# PowerSup24V18-20A.net
KiCad netlist of a schematic drawn in EAGLE
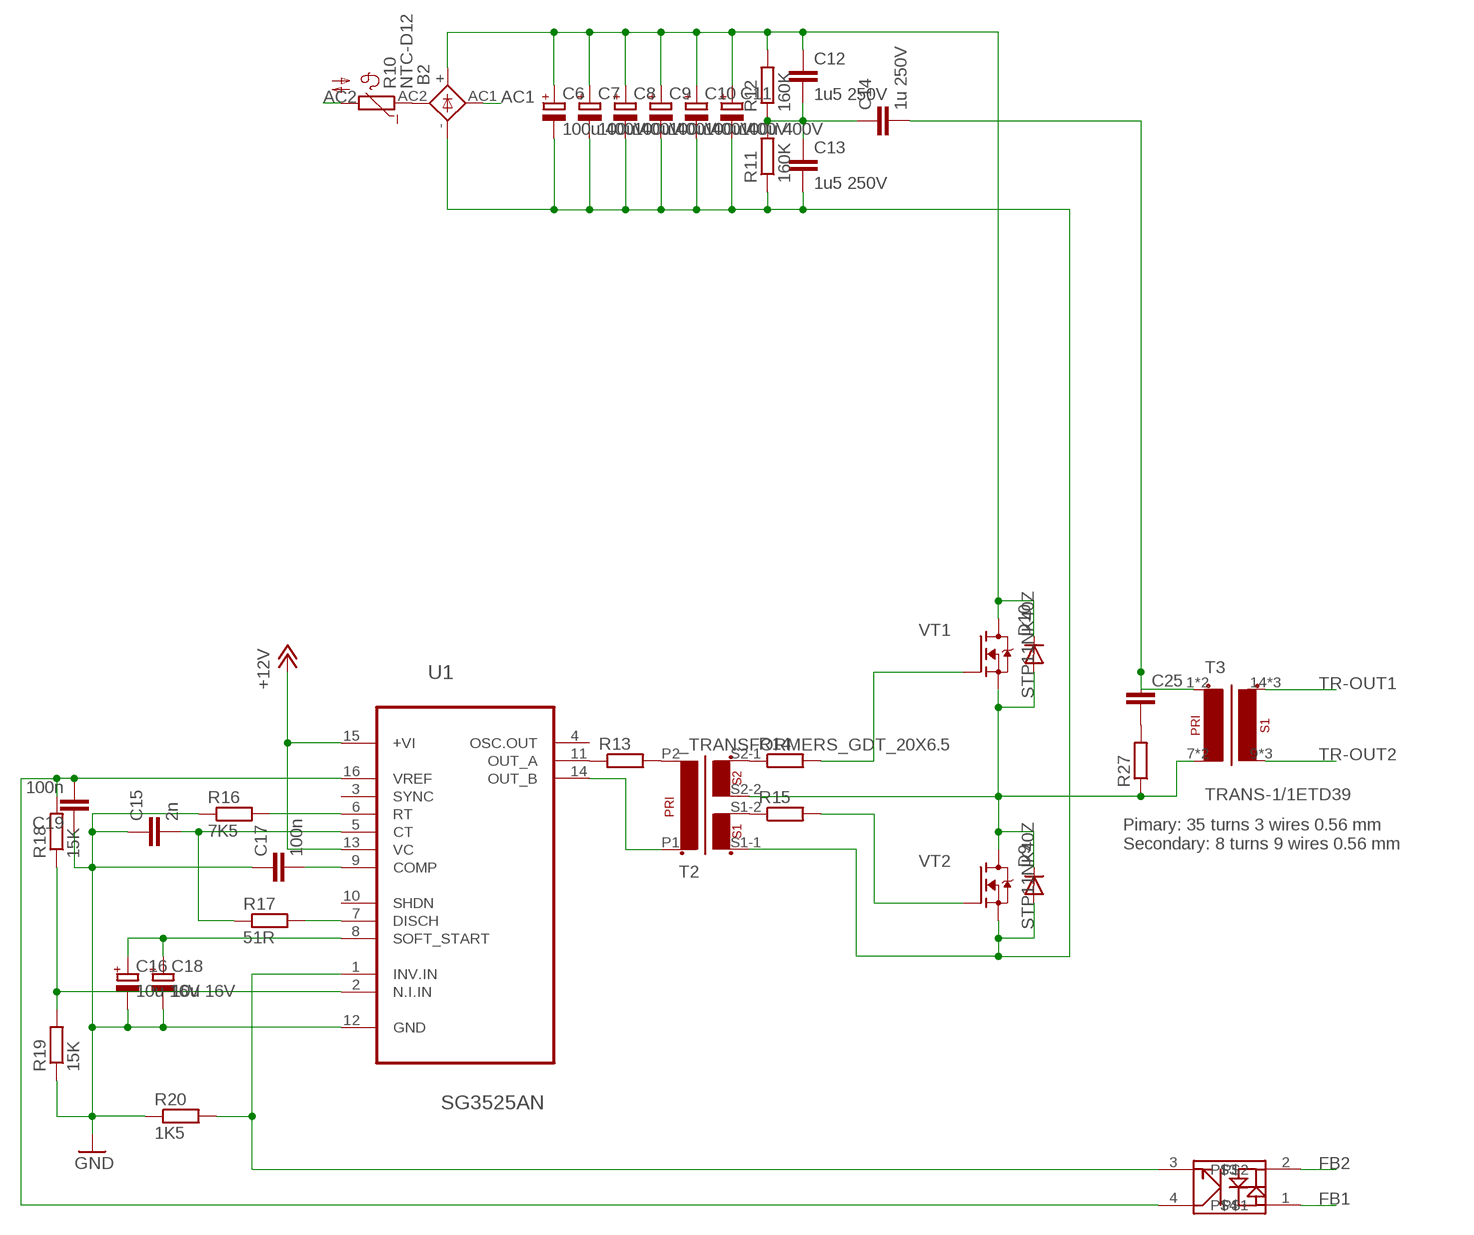
[diagram p0: schematic, sheet 1]
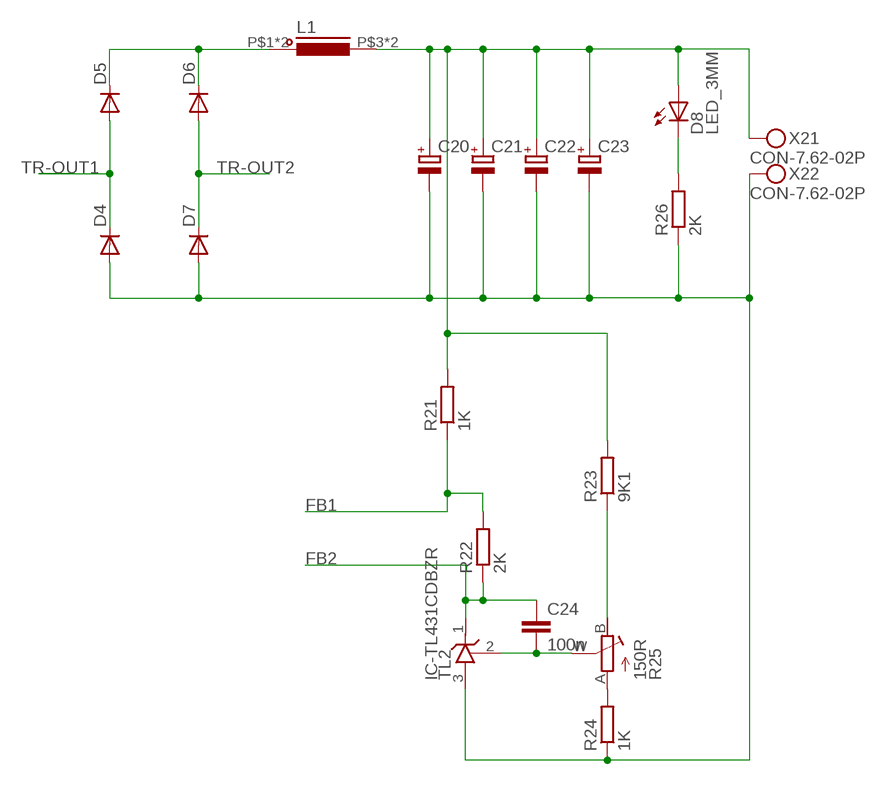
[diagram p1: schematic, sheet 2]
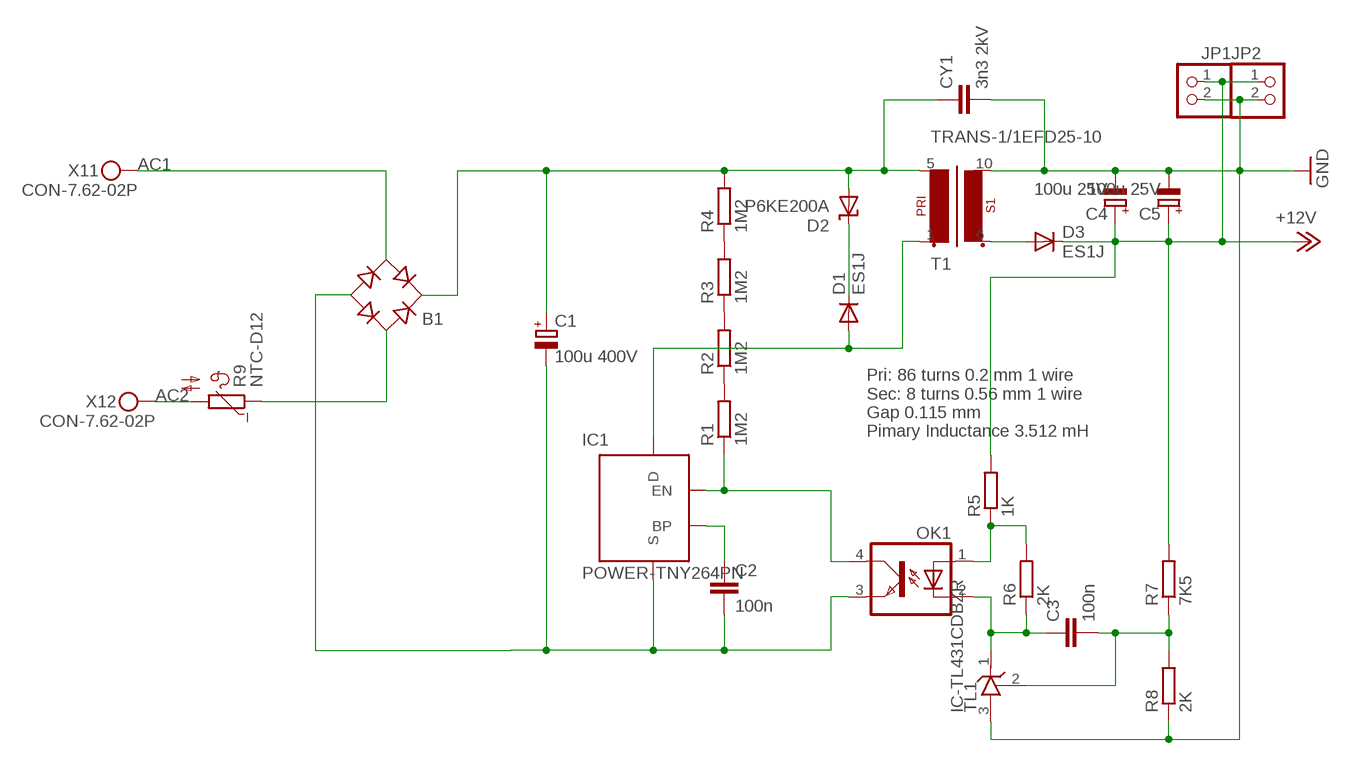
[diagram p2: schematic, sheet 3]

(export (version "E")
  (design (tool "Eeschema 10.0.6"))
  (components
    (comp (ref "B2")
      (value "RECTIFIERKBL")
      (footprint "eagle-import:KBL")
      (libsource (lib "eagle-import") (part "RECTIFIERKBL"))
    )
    (comp (ref "C6")
      (value "100u 400V")
      (footprint "eagle-import:E7,5-18")
      (libsource (lib "eagle-import") (part "CPOL-EUE7.5-18"))
    )
    (comp (ref "C7")
      (value "100u 400V")
      (footprint "eagle-import:E7,5-18")
      (libsource (lib "eagle-import") (part "CPOL-EUE7.5-18"))
    )
    (comp (ref "C8")
      (value "100u 400V")
      (footprint "eagle-import:E7,5-18")
      (libsource (lib "eagle-import") (part "CPOL-EUE7.5-18"))
    )
    (comp (ref "C9")
      (value "100u 400V")
      (footprint "eagle-import:E7,5-18")
      (libsource (lib "eagle-import") (part "CPOL-EUE7.5-18"))
    )
    (comp (ref "C10")
      (value "100u 400V")
      (footprint "eagle-import:E7,5-18")
      (libsource (lib "eagle-import") (part "CPOL-EUE7.5-18"))
    )
    (comp (ref "C11")
      (value "100u 400V")
      (footprint "eagle-import:E7,5-18")
      (libsource (lib "eagle-import") (part "CPOL-EUE7.5-18"))
    )
    (comp (ref "C12")
      (value "1u5 250V")
      (footprint "eagle-import:C225-074X268")
      (libsource (lib "eagle-import") (part "C-EU225-074X268"))
    )
    (comp (ref "C13")
      (value "1u5 250V")
      (footprint "eagle-import:C225-074X268")
      (libsource (lib "eagle-import") (part "C-EU225-074X268"))
    )
    (comp (ref "C14")
      (value "1u 250V")
      (footprint "eagle-import:C225-074X268")
      (libsource (lib "eagle-import") (part "C-EU225-074X268"))
    )
    (comp (ref "C15")
      (value "2n")
      (footprint "eagle-import:C0805")
      (libsource (lib "eagle-import") (part "CAP_0805"))
    )
    (comp (ref "C16")
      (value "10u 16V")
      (footprint "eagle-import:CT3528")
      (libsource (lib "eagle-import") (part "CAP-POL_3528"))
    )
    (comp (ref "C17")
      (value "100n")
      (footprint "eagle-import:C0805")
      (libsource (lib "eagle-import") (part "CAP_0805"))
    )
    (comp (ref "C18")
      (value "10u 16V")
      (footprint "eagle-import:CT3528")
      (libsource (lib "eagle-import") (part "CAP-POL_3528"))
    )
    (comp (ref "C19")
      (value "100n")
      (footprint "eagle-import:C0805")
      (libsource (lib "eagle-import") (part "CAP_0805"))
    )
    (comp (ref "C25")
      (value "CAP_C50-024X044")
      (footprint "eagle-import:C050-024X044")
      (libsource (lib "eagle-import") (part "CAP_C50-024X044"))
    )
    (comp (ref "D9")
      (value "DIODE_ES1J")
      (footprint "eagle-import:DO214AC")
      (libsource (lib "eagle-import") (part "DIODE_ES1J"))
    )
    (comp (ref "D10")
      (value "DIODE_ES1J")
      (footprint "eagle-import:DO214AC")
      (libsource (lib "eagle-import") (part "DIODE_ES1J"))
    )
    (comp (ref "R10")
      (value "NTC-D12")
      (footprint "eagle-import:NTC-D12")
      (libsource (lib "eagle-import") (part "NTC-D12"))
    )
    (comp (ref "R11")
      (value "160K")
      (footprint "eagle-import:MF-0125")
      (libsource (lib "eagle-import") (part "R_MF-0125"))
    )
    (comp (ref "R12")
      (value "160K")
      (footprint "eagle-import:MF-0125")
      (libsource (lib "eagle-import") (part "R_MF-0125"))
    )
    (comp (ref "R13")
      (value "R_1206")
      (footprint "eagle-import:R1206")
      (libsource (lib "eagle-import") (part "R_1206"))
    )
    (comp (ref "R14")
      (value "R_1206")
      (footprint "eagle-import:R1206")
      (libsource (lib "eagle-import") (part "R_1206"))
    )
    (comp (ref "R15")
      (value "R_1206")
      (footprint "eagle-import:R1206")
      (libsource (lib "eagle-import") (part "R_1206"))
    )
    (comp (ref "R16")
      (value "7K5")
      (footprint "eagle-import:R0805")
      (libsource (lib "eagle-import") (part "R_0805"))
    )
    (comp (ref "R17")
      (value "51R")
      (footprint "eagle-import:R0805")
      (libsource (lib "eagle-import") (part "R_0805"))
    )
    (comp (ref "R18")
      (value "15K")
      (footprint "eagle-import:R0805")
      (libsource (lib "eagle-import") (part "R_0805"))
    )
    (comp (ref "R19")
      (value "15K")
      (footprint "eagle-import:R0805")
      (libsource (lib "eagle-import") (part "R_0805"))
    )
    (comp (ref "R20")
      (value "1K5")
      (footprint "eagle-import:R0805")
      (libsource (lib "eagle-import") (part "R_0805"))
    )
    (comp (ref "R27")
      (value "R_MF-2")
      (footprint "eagle-import:MF-2")
      (libsource (lib "eagle-import") (part "R_MF-2"))
    )
    (comp (ref "T2")
      (value "_TRANSFORMERS_GDT_20X6.5")
      (footprint "eagle-import:_TRANSFORMERS_GDT_20X6.5")
      (libsource (lib "eagle-import") (part "_TRANSFORMERS_GDT_20X6.5"))
    )
    (comp (ref "T3")
      (value "TRANS-1/1ETD39")
      (footprint "eagle-import:ETD39")
      (libsource (lib "eagle-import") (part "TRANS-1/1ETD39"))
    )
    (comp (ref "U$1")
      (value "OPTO-EL3H4(TA)-VG")
      (footprint "eagle-import:SSOP4")
      (libsource (lib "eagle-import") (part "OPTO-EL3H4(TA)-VG"))
    )
    (comp (ref "U1")
      (value "SG3525AN")
      (footprint "eagle-import:DIP254P762X510-16")
      (libsource (lib "eagle-import") (part "SG3525AN"))
    )
    (comp (ref "VT1")
      (value "STP11NK40Z")
      (footprint "eagle-import:TO-220V")
      (libsource (lib "eagle-import") (part "FET-NTO-220"))
    )
    (comp (ref "VT2")
      (value "STP11NK40Z")
      (footprint "eagle-import:TO-220V")
      (libsource (lib "eagle-import") (part "FET-NTO-220"))
    )
    (comp (ref "B1")
      (value "RB1A")
      (footprint "eagle-import:RB1A")
      (libsource (lib "eagle-import") (part "RB1A"))
    )
    (comp (ref "C1")
      (value "100u 400V")
      (footprint "eagle-import:E7,5-18")
      (libsource (lib "eagle-import") (part "CPOL-EUE7.5-18"))
    )
    (comp (ref "C2")
      (value "100n")
      (footprint "eagle-import:C0805")
      (libsource (lib "eagle-import") (part "CAP_0805"))
    )
    (comp (ref "C3")
      (value "100n")
      (footprint "eagle-import:C0805")
      (libsource (lib "eagle-import") (part "CAP_0805"))
    )
    (comp (ref "C4")
      (value "100u 25V")
      (footprint "eagle-import:E2,5-7")
      (libsource (lib "eagle-import") (part "CAP-POL_E2.5-7"))
    )
    (comp (ref "C5")
      (value "100u 25V")
      (footprint "eagle-import:E2,5-7")
      (libsource (lib "eagle-import") (part "CAP-POL_E2.5-7"))
    )
    (comp (ref "CY1")
      (value "3n3 2kV")
      (footprint "eagle-import:YC7B5")
      (libsource (lib "eagle-import") (part "CYYC7B5"))
    )
    (comp (ref "D1")
      (value "ES1J")
      (footprint "eagle-import:DO214AC")
      (libsource (lib "eagle-import") (part "DIODE_ES1J"))
    )
    (comp (ref "D2")
      (value "P6KE200A")
      (footprint "eagle-import:DO15-12")
      (libsource (lib "eagle-import") (part "SUPRESSORDO-204AC"))
    )
    (comp (ref "D3")
      (value "ES1J")
      (footprint "eagle-import:DO214AC")
      (libsource (lib "eagle-import") (part "DIODE_ES1J"))
    )
    (comp (ref "IC1")
      (value "POWER-TNY264PN")
      (footprint "eagle-import:DIP-8B")
      (libsource (lib "eagle-import") (part "POWER-TNY264PN"))
    )
    (comp (ref "JP1")
      (value "PINHD-1X2")
      (footprint "eagle-import:1X02")
      (libsource (lib "eagle-import") (part "PINHD-1X2"))
    )
    (comp (ref "JP2")
      (value "PINHD-1X2")
      (footprint "eagle-import:1X02")
      (libsource (lib "eagle-import") (part "PINHD-1X2"))
    )
    (comp (ref "OK1")
      (value "OPTOTRANSPC817")
      (footprint "eagle-import:DIL04")
      (fields (field (name "MPN") "PC817X4J000F"))
      (libsource (lib "eagle-import") (part "OPTOTRANSPC817"))
    )
    (comp (ref "R1")
      (value "1M2")
      (footprint "eagle-import:R0805")
      (libsource (lib "eagle-import") (part "R_0805"))
    )
    (comp (ref "R2")
      (value "1M2")
      (footprint "eagle-import:R0805")
      (libsource (lib "eagle-import") (part "R_0805"))
    )
    (comp (ref "R3")
      (value "1M2")
      (footprint "eagle-import:R0805")
      (libsource (lib "eagle-import") (part "R_0805"))
    )
    (comp (ref "R4")
      (value "1M2")
      (footprint "eagle-import:R0805")
      (libsource (lib "eagle-import") (part "R_0805"))
    )
    (comp (ref "R5")
      (value "1K")
      (footprint "eagle-import:R0805")
      (libsource (lib "eagle-import") (part "R_0805"))
    )
    (comp (ref "R6")
      (value "2K")
      (footprint "eagle-import:R0805")
      (libsource (lib "eagle-import") (part "R_0805"))
    )
    (comp (ref "R7")
      (value "7K5")
      (footprint "eagle-import:R0805")
      (libsource (lib "eagle-import") (part "R_0805"))
    )
    (comp (ref "R8")
      (value "2K")
      (footprint "eagle-import:R0805")
      (libsource (lib "eagle-import") (part "R_0805"))
    )
    (comp (ref "R9")
      (value "NTC-D12")
      (footprint "eagle-import:NTC-D12")
      (libsource (lib "eagle-import") (part "NTC-D12"))
    )
    (comp (ref "T1")
      (value "TRANS-1/1EFD25-10")
      (footprint "eagle-import:EFD25_10PIN")
      (libsource (lib "eagle-import") (part "TRANS-1/1EFD25-10"))
    )
    (comp (ref "TL1")
      (value "IC-TL431CDBZR")
      (footprint "eagle-import:SOT23")
      (libsource (lib "eagle-import") (part "IC-TL431CDBZR"))
    )
    (comp (ref "X1")
      (value "CON-7.62-02P")
      (footprint "eagle-import:KF25C-7.62-02P-13")
      (libsource (lib "eagle-import") (part "CON-7.62-02P"))
    )
    (comp (ref "C20")
      (value "CPOL-EUE5-13")
      (footprint "eagle-import:E5-13")
      (libsource (lib "eagle-import") (part "CPOL-EUE5-13"))
    )
    (comp (ref "C21")
      (value "CPOL-EUE5-13")
      (footprint "eagle-import:E5-13")
      (libsource (lib "eagle-import") (part "CPOL-EUE5-13"))
    )
    (comp (ref "C22")
      (value "CPOL-EUE5-13")
      (footprint "eagle-import:E5-13")
      (libsource (lib "eagle-import") (part "CPOL-EUE5-13"))
    )
    (comp (ref "C23")
      (value "CPOL-EUE5-13")
      (footprint "eagle-import:E5-13")
      (libsource (lib "eagle-import") (part "CPOL-EUE5-13"))
    )
    (comp (ref "C24")
      (value "100n")
      (footprint "eagle-import:C0805")
      (libsource (lib "eagle-import") (part "CAP_0805"))
    )
    (comp (ref "D4")
      (value "DIODE_TO-220-2")
      (footprint "eagle-import:TO220ACS")
      (libsource (lib "eagle-import") (part "DIODE_TO-220-2"))
    )
    (comp (ref "D5")
      (value "DIODE_TO-220-2")
      (footprint "eagle-import:TO220ACS")
      (libsource (lib "eagle-import") (part "DIODE_TO-220-2"))
    )
    (comp (ref "D6")
      (value "DIODE_TO-220-2")
      (footprint "eagle-import:TO220ACS")
      (libsource (lib "eagle-import") (part "DIODE_TO-220-2"))
    )
    (comp (ref "D7")
      (value "DIODE_TO-220-2")
      (footprint "eagle-import:TO220ACS")
      (libsource (lib "eagle-import") (part "DIODE_TO-220-2"))
    )
    (comp (ref "D8")
      (value "LED_3MM")
      (footprint "eagle-import:LED3MM")
      (libsource (lib "eagle-import") (part "LED_3MM"))
    )
    (comp (ref "L1")
      (value "INDUCTORD26.7")
      (footprint "eagle-import:D26.9_14.7_11.2")
      (libsource (lib "eagle-import") (part "INDUCTORD26.7"))
    )
    (comp (ref "R21")
      (value "1K")
      (footprint "eagle-import:R0805")
      (libsource (lib "eagle-import") (part "R_0805"))
    )
    (comp (ref "R22")
      (value "2K")
      (footprint "eagle-import:R0805")
      (libsource (lib "eagle-import") (part "R_0805"))
    )
    (comp (ref "R23")
      (value "9K1")
      (footprint "eagle-import:R0805")
      (libsource (lib "eagle-import") (part "R_0805"))
    )
    (comp (ref "R24")
      (value "1K")
      (footprint "eagle-import:R0805")
      (libsource (lib "eagle-import") (part "R_0805"))
    )
    (comp (ref "R25")
      (value "150R")
      (footprint "eagle-import:RJ9W")
      (libsource (lib "eagle-import") (part "R_POTTURN-X"))
    )
    (comp (ref "R26")
      (value "2K")
      (footprint "eagle-import:R0805")
      (libsource (lib "eagle-import") (part "R_0805"))
    )
    (comp (ref "TL2")
      (value "IC-TL431CDBZR")
      (footprint "eagle-import:SOT23")
      (libsource (lib "eagle-import") (part "IC-TL431CDBZR"))
    )
    (comp (ref "X2")
      (value "CON-7.62-02P")
      (footprint "eagle-import:KF25C-7.62-02P-13")
      (libsource (lib "eagle-import") (part "CON-7.62-02P"))
    )
  )
  (nets
    (net (code "1") (name "+12V") (class "Default")
      (node (ref "C4") (pin "+") (pinfunction "+_+") (pintype "passive"))
      (node (ref "C5") (pin "+") (pinfunction "+_+") (pintype "passive"))
      (node (ref "D3") (pin "C") (pinfunction "C_C") (pintype "passive"))
      (node (ref "JP1") (pin "1") (pinfunction "1_1") (pintype "passive"))
      (node (ref "JP2") (pin "1") (pinfunction "1_1") (pintype "passive"))
      (node (ref "R5") (pin "2") (pinfunction "2_2") (pintype "passive"))
      (node (ref "R7") (pin "2") (pinfunction "2_2") (pintype "passive"))
      (node (ref "U1") (pin "13") (pinfunction "VC_13") (pintype "passive"))
      (node (ref "U1") (pin "15") (pinfunction "+VI_15") (pintype "power_in"))
    )
    (net (code "2") (name "AC1") (class "Default")
      (node (ref "B1") (pin "AC2") (pinfunction "AC2_AC2") (pintype "passive"))
      (node (ref "B2") (pin "AC1") (pinfunction "AC2_AC1") (pintype "passive"))
      (node (ref "X1") (pin "P$1") (pinfunction "KL_P$1") (pintype "passive"))
    )
    (net (code "3") (name "AC2") (class "Default")
      (node (ref "R10") (pin "2") (pinfunction "2_2") (pintype "passive"))
      (node (ref "R9") (pin "2") (pinfunction "2_2") (pintype "passive"))
      (node (ref "X1") (pin "P$2") (pinfunction "KL_P$2") (pintype "passive"))
    )
    (net (code "4") (name "FB1") (class "Default")
      (node (ref "R21") (pin "1") (pinfunction "1_1") (pintype "passive"))
      (node (ref "R22") (pin "2") (pinfunction "2_2") (pintype "passive"))
      (node (ref "U$1") (pin "1") (pinfunction "P$1_1") (pintype "bidirectional"))
    )
    (net (code "5") (name "FB2") (class "Default")
      (node (ref "C24") (pin "1") (pinfunction "1_1") (pintype "passive"))
      (node (ref "R22") (pin "1") (pinfunction "1_1") (pintype "passive"))
      (node (ref "TL2") (pin "1") (pinfunction "C_1") (pintype "passive"))
      (node (ref "U$1") (pin "2") (pinfunction "P$2_2") (pintype "bidirectional"))
    )
    (net (code "6") (name "GND") (class "Default")
      (node (ref "C15") (pin "1") (pinfunction "1_1") (pintype "passive"))
      (node (ref "C16") (pin "-") (pinfunction "-_-") (pintype "passive"))
      (node (ref "C17") (pin "1") (pinfunction "1_1") (pintype "passive"))
      (node (ref "C18") (pin "-") (pinfunction "-_-") (pintype "passive"))
      (node (ref "C19") (pin "1") (pinfunction "1_1") (pintype "passive"))
      (node (ref "C4") (pin "-") (pinfunction "-_-") (pintype "passive"))
      (node (ref "C5") (pin "-") (pinfunction "-_-") (pintype "passive"))
      (node (ref "CY1") (pin "2") (pinfunction "2_2") (pintype "passive"))
      (node (ref "JP1") (pin "2") (pinfunction "2_2") (pintype "passive"))
      (node (ref "JP2") (pin "2") (pinfunction "2_2") (pintype "passive"))
      (node (ref "R16") (pin "1") (pinfunction "1_1") (pintype "passive"))
      (node (ref "R19") (pin "1") (pinfunction "1_1") (pintype "passive"))
      (node (ref "R20") (pin "1") (pinfunction "1_1") (pintype "passive"))
      (node (ref "R8") (pin "1") (pinfunction "1_1") (pintype "passive"))
      (node (ref "T1") (pin "10") (pinfunction "S1-2_10") (pintype "passive"))
      (node (ref "TL1") (pin "3") (pinfunction "A_3") (pintype "passive"))
      (node (ref "U1") (pin "12") (pinfunction "GND_12") (pintype "passive"))
    )
    (net (code "7") (name "Net-(B1-PadAC1)") (class "Default")
      (node (ref "B1") (pin "AC1") (pinfunction "AC1_AC1") (pintype "passive"))
      (node (ref "R9") (pin "1") (pinfunction "1_1") (pintype "passive"))
    )
    (net (code "8") (name "Net-(B2-AC1)") (class "Default")
      (node (ref "B2") (pin "AC2") (pinfunction "AC1_AC2") (pintype "passive"))
      (node (ref "R10") (pin "1") (pinfunction "1_1") (pintype "passive"))
    )
    (net (code "9") (name "Net-(C12-Pad2)") (class "Default")
      (node (ref "C12") (pin "2") (pinfunction "2_2") (pintype "passive"))
      (node (ref "C13") (pin "1") (pinfunction "1_1") (pintype "passive"))
      (node (ref "C14") (pin "1") (pinfunction "1_1") (pintype "passive"))
      (node (ref "R11") (pin "2") (pinfunction "2_2") (pintype "passive"))
      (node (ref "R12") (pin "1") (pinfunction "1_1") (pintype "passive"))
    )
    (net (code "10") (name "Net-(C14-Pad2)") (class "Default")
      (node (ref "C14") (pin "2") (pinfunction "2_2") (pintype "passive"))
      (node (ref "C25") (pin "1") (pinfunction "1_1") (pintype "passive"))
      (node (ref "T3") (pin "1") (pinfunction "P1-1_1") (pintype "passive"))
      (node (ref "T3") (pin "2") (pinfunction "P1-1_2") (pintype "passive"))
    )
    (net (code "11") (name "Net-(C25-Pad2)") (class "Default")
      (node (ref "C25") (pin "2") (pinfunction "2_2") (pintype "passive"))
      (node (ref "R27") (pin "2") (pinfunction "2_2") (pintype "passive"))
    )
    (net (code "12") (name "Net-(D1-PadC)") (class "Default")
      (node (ref "D1") (pin "C") (pinfunction "C_C") (pintype "passive"))
      (node (ref "D2") (pin "C") (pinfunction "C_C") (pintype "passive"))
    )
    (net (code "13") (name "Net-(D5-PadC)") (class "Default")
      (node (ref "D5") (pin "C") (pinfunction "C_C") (pintype "passive"))
      (node (ref "D6") (pin "C") (pinfunction "C_C") (pintype "passive"))
      (node (ref "L1") (pin "P$1") (pinfunction "1_P$1") (pintype "passive"))
      (node (ref "L1") (pin "P$2") (pinfunction "1_P$2") (pintype "passive"))
    )
    (net (code "14") (name "Net-(D8-C)") (class "Default")
      (node (ref "D8") (pin "K") (pinfunction "C_K") (pintype "passive"))
      (node (ref "R26") (pin "2") (pinfunction "2_2") (pintype "passive"))
    )
    (net (code "15") (name "Net-(IC1-BP)") (class "Default")
      (node (ref "C2") (pin "1") (pinfunction "1_1") (pintype "passive"))
      (node (ref "IC1") (pin "1") (pinfunction "BP_1") (pintype "input"))
    )
    (net (code "16") (name "Net-(IC1-D)") (class "Default")
      (node (ref "D1") (pin "A") (pinfunction "A_A") (pintype "passive"))
      (node (ref "IC1") (pin "5") (pinfunction "D_5") (pintype "input"))
      (node (ref "T1") (pin "1") (pinfunction "P1-1_1") (pintype "passive"))
    )
    (net (code "17") (name "Net-(IC1-EN)") (class "Default")
      (node (ref "IC1") (pin "4") (pinfunction "EN_4") (pintype "input"))
      (node (ref "OK1") (pin "4") (pinfunction "COL_4") (pintype "passive"))
      (node (ref "R1") (pin "1") (pinfunction "1_1") (pintype "passive"))
    )
    (net (code "18") (name "Net-(OK1-A)") (class "Default")
      (node (ref "OK1") (pin "1") (pinfunction "A_1") (pintype "passive"))
      (node (ref "R5") (pin "1") (pinfunction "1_1") (pintype "passive"))
      (node (ref "R6") (pin "2") (pinfunction "2_2") (pintype "passive"))
    )
    (net (code "19") (name "Net-(OK1-C)") (class "Default")
      (node (ref "C3") (pin "1") (pinfunction "1_1") (pintype "passive"))
      (node (ref "OK1") (pin "2") (pinfunction "C_2") (pintype "passive"))
      (node (ref "R6") (pin "1") (pinfunction "1_1") (pintype "passive"))
      (node (ref "TL1") (pin "1") (pinfunction "C_1") (pintype "passive"))
    )
    (net (code "20") (name "Net-(OK1-EMIT)") (class "Default")
      (node (ref "B1") (pin "-") (pinfunction "-_-") (pintype "passive"))
      (node (ref "C1") (pin "-") (pinfunction "-_-") (pintype "passive"))
      (node (ref "C2") (pin "2") (pinfunction "2_2") (pintype "passive"))
      (node (ref "IC1") (pin "2") (pinfunction "S_2") (pintype "input"))
      (node (ref "IC1") (pin "3") (pinfunction "S_3") (pintype "input"))
      (node (ref "IC1") (pin "7") (pinfunction "S_7") (pintype "input"))
      (node (ref "IC1") (pin "8") (pinfunction "S_8") (pintype "input"))
      (node (ref "OK1") (pin "3") (pinfunction "EMIT_3") (pintype "passive"))
    )
    (net (code "21") (name "Net-(R1-Pad2)") (class "Default")
      (node (ref "R1") (pin "2") (pinfunction "2_2") (pintype "passive"))
      (node (ref "R2") (pin "1") (pinfunction "1_1") (pintype "passive"))
    )
    (net (code "22") (name "Net-(R2-Pad2)") (class "Default")
      (node (ref "R2") (pin "2") (pinfunction "2_2") (pintype "passive"))
      (node (ref "R3") (pin "1") (pinfunction "1_1") (pintype "passive"))
    )
    (net (code "23") (name "Net-(R3-Pad2)") (class "Default")
      (node (ref "R3") (pin "2") (pinfunction "2_2") (pintype "passive"))
      (node (ref "R4") (pin "1") (pinfunction "1_1") (pintype "passive"))
    )
    (net (code "24") (name "Net-(R14-Pad1)") (class "Default")
      (node (ref "R14") (pin "1") (pinfunction "1_1") (pintype "passive"))
      (node (ref "T2") (pin "S2-1") (pinfunction "S2-1_S2-1") (pintype "passive"))
    )
    (net (code "25") (name "Net-(R15-Pad1)") (class "Default")
      (node (ref "R15") (pin "1") (pinfunction "1_1") (pintype "passive"))
      (node (ref "T2") (pin "S1-2") (pinfunction "S1-2_S1-2") (pintype "passive"))
    )
    (net (code "26") (name "Net-(R24-Pad2)") (class "Default")
      (node (ref "R24") (pin "2") (pinfunction "2_2") (pintype "passive"))
      (node (ref "R25") (pin "A") (pinfunction "A_A") (pintype "passive"))
    )
    (net (code "27") (name "Net-(R25-E)") (class "Default")
      (node (ref "R23") (pin "1") (pinfunction "1_1") (pintype "passive"))
      (node (ref "R25") (pin "B") (pinfunction "E_B") (pintype "passive"))
    )
    (net (code "28") (name "Net-(R25-S)") (class "Default")
      (node (ref "C24") (pin "2") (pinfunction "2_2") (pintype "passive"))
      (node (ref "R25") (pin "W") (pinfunction "S_W") (pintype "passive"))
      (node (ref "TL2") (pin "2") (pinfunction "R_2") (pintype "passive"))
    )
    (net (code "29") (name "Net-(T1-P1-2)") (class "Default")
      (node (ref "B1") (pin "+") (pinfunction "+_+") (pintype "passive"))
      (node (ref "C1") (pin "+") (pinfunction "+_+") (pintype "passive"))
      (node (ref "CY1") (pin "1") (pinfunction "1_1") (pintype "passive"))
      (node (ref "D2") (pin "A") (pinfunction "A_A") (pintype "passive"))
      (node (ref "R4") (pin "2") (pinfunction "2_2") (pintype "passive"))
      (node (ref "T1") (pin "5") (pinfunction "P1-2_5") (pintype "passive"))
    )
    (net (code "30") (name "Net-(T1-S1-1)") (class "Default")
      (node (ref "D3") (pin "A") (pinfunction "A_A") (pintype "passive"))
      (node (ref "T1") (pin "6") (pinfunction "S1-1_6") (pintype "passive"))
    )
    (net (code "31") (name "Net-(T2-P1-1)") (class "Default")
      (node (ref "T2") (pin "P1") (pinfunction "P1-1_P1") (pintype "passive"))
      (node (ref "U1") (pin "14") (pinfunction "OUT_B_14") (pintype "output"))
    )
    (net (code "32") (name "Net-(T2-P1-2)") (class "Default")
      (node (ref "R13") (pin "2") (pinfunction "2_2") (pintype "passive"))
      (node (ref "T2") (pin "P2") (pinfunction "P1-2_P2") (pintype "passive"))
    )
    (net (code "33") (name "Net-(TL1-R)") (class "Default")
      (node (ref "C3") (pin "2") (pinfunction "2_2") (pintype "passive"))
      (node (ref "R7") (pin "1") (pinfunction "1_1") (pintype "passive"))
      (node (ref "R8") (pin "2") (pinfunction "2_2") (pintype "passive"))
      (node (ref "TL1") (pin "2") (pinfunction "R_2") (pintype "passive"))
    )
    (net (code "34") (name "Net-(TL2-A)") (class "Default")
      (node (ref "C20") (pin "-") (pinfunction "-_-") (pintype "passive"))
      (node (ref "C21") (pin "-") (pinfunction "-_-") (pintype "passive"))
      (node (ref "C22") (pin "-") (pinfunction "-_-") (pintype "passive"))
      (node (ref "C23") (pin "-") (pinfunction "-_-") (pintype "passive"))
      (node (ref "D4") (pin "A") (pinfunction "A_A") (pintype "passive"))
      (node (ref "D7") (pin "A") (pinfunction "A_A") (pintype "passive"))
      (node (ref "R24") (pin "1") (pinfunction "1_1") (pintype "passive"))
      (node (ref "R26") (pin "1") (pinfunction "1_1") (pintype "passive"))
      (node (ref "TL2") (pin "3") (pinfunction "A_3") (pintype "passive"))
      (node (ref "X2") (pin "P$2") (pinfunction "KL_P$2") (pintype "passive"))
    )
    (net (code "35") (name "Net-(U$1-P$3)") (class "Default")
      (node (ref "R20") (pin "2") (pinfunction "2_2") (pintype "passive"))
      (node (ref "U$1") (pin "3") (pinfunction "P$3_3") (pintype "bidirectional"))
      (node (ref "U1") (pin "1") (pinfunction "INV.IN_1") (pintype "input"))
    )
    (net (code "36") (name "Net-(U$1-P$4)") (class "Default")
      (node (ref "C19") (pin "2") (pinfunction "2_2") (pintype "passive"))
      (node (ref "R18") (pin "2") (pinfunction "2_2") (pintype "passive"))
      (node (ref "U$1") (pin "4") (pinfunction "P$4_4") (pintype "bidirectional"))
      (node (ref "U1") (pin "16") (pinfunction "VREF_16") (pintype "passive"))
    )
    (net (code "37") (name "Net-(U1-COMP)") (class "Default")
      (node (ref "C17") (pin "2") (pinfunction "2_2") (pintype "passive"))
      (node (ref "U1") (pin "9") (pinfunction "COMP_9") (pintype "passive"))
    )
    (net (code "38") (name "Net-(U1-CT)") (class "Default")
      (node (ref "C15") (pin "2") (pinfunction "2_2") (pintype "passive"))
      (node (ref "R17") (pin "1") (pinfunction "1_1") (pintype "passive"))
      (node (ref "U1") (pin "5") (pinfunction "CT_5") (pintype "passive"))
    )
    (net (code "39") (name "Net-(U1-DISCH)") (class "Default")
      (node (ref "R17") (pin "2") (pinfunction "2_2") (pintype "passive"))
      (node (ref "U1") (pin "7") (pinfunction "DISCH_7") (pintype "passive"))
    )
    (net (code "40") (name "Net-(U1-N.I.IN)") (class "Default")
      (node (ref "R18") (pin "1") (pinfunction "1_1") (pintype "passive"))
      (node (ref "R19") (pin "2") (pinfunction "2_2") (pintype "passive"))
      (node (ref "U1") (pin "2") (pinfunction "N.I.IN_2") (pintype "input"))
    )
    (net (code "41") (name "Net-(U1-OUT_A)") (class "Default")
      (node (ref "R13") (pin "1") (pinfunction "1_1") (pintype "passive"))
      (node (ref "U1") (pin "11") (pinfunction "OUT_A_11") (pintype "output"))
    )
    (net (code "42") (name "Net-(U1-RT)") (class "Default")
      (node (ref "R16") (pin "2") (pinfunction "2_2") (pintype "passive"))
      (node (ref "U1") (pin "6") (pinfunction "RT_6") (pintype "passive"))
    )
    (net (code "43") (name "Net-(U1-SOFT_START)") (class "Default")
      (node (ref "C16") (pin "+") (pinfunction "+_+") (pintype "passive"))
      (node (ref "C18") (pin "+") (pinfunction "+_+") (pintype "passive"))
      (node (ref "U1") (pin "8") (pinfunction "SOFT_START_8") (pintype "passive"))
    )
    (net (code "44") (name "Net-(VT1-D)") (class "Default")
      (node (ref "B2") (pin "+") (pinfunction "+_+") (pintype "passive"))
      (node (ref "C10") (pin "+") (pinfunction "+_+") (pintype "passive"))
      (node (ref "C11") (pin "+") (pinfunction "+_+") (pintype "passive"))
      (node (ref "C12") (pin "1") (pinfunction "1_1") (pintype "passive"))
      (node (ref "C6") (pin "+") (pinfunction "+_+") (pintype "passive"))
      (node (ref "C7") (pin "+") (pinfunction "+_+") (pintype "passive"))
      (node (ref "C8") (pin "+") (pinfunction "+_+") (pintype "passive"))
      (node (ref "C9") (pin "+") (pinfunction "+_+") (pintype "passive"))
      (node (ref "D10") (pin "C") (pinfunction "C_C") (pintype "passive"))
      (node (ref "R12") (pin "2") (pinfunction "2_2") (pintype "passive"))
      (node (ref "VT1") (pin "2") (pinfunction "D_2") (pintype "passive"))
    )
    (net (code "45") (name "Net-(VT1-G)") (class "Default")
      (node (ref "R14") (pin "2") (pinfunction "2_2") (pintype "passive"))
      (node (ref "VT1") (pin "1") (pinfunction "G_1") (pintype "passive"))
    )
    (net (code "46") (name "Net-(VT1-S)") (class "Default")
      (node (ref "D10") (pin "A") (pinfunction "A_A") (pintype "passive"))
      (node (ref "D9") (pin "C") (pinfunction "C_C") (pintype "passive"))
      (node (ref "R27") (pin "1") (pinfunction "1_1") (pintype "passive"))
      (node (ref "T2") (pin "S2-2") (pinfunction "S2-2_S2-2") (pintype "passive"))
      (node (ref "T3") (pin "7") (pinfunction "P1-2_7") (pintype "passive"))
      (node (ref "T3") (pin "8") (pinfunction "P1-2_8") (pintype "passive"))
      (node (ref "VT1") (pin "3") (pinfunction "S_3") (pintype "passive"))
      (node (ref "VT2") (pin "2") (pinfunction "D_2") (pintype "passive"))
    )
    (net (code "47") (name "Net-(VT2-G)") (class "Default")
      (node (ref "R15") (pin "2") (pinfunction "2_2") (pintype "passive"))
      (node (ref "VT2") (pin "1") (pinfunction "G_1") (pintype "passive"))
    )
    (net (code "48") (name "Net-(VT2-S)") (class "Default")
      (node (ref "B2") (pin "-") (pinfunction "-_-") (pintype "passive"))
      (node (ref "C10") (pin "-") (pinfunction "-_-") (pintype "passive"))
      (node (ref "C11") (pin "-") (pinfunction "-_-") (pintype "passive"))
      (node (ref "C13") (pin "2") (pinfunction "2_2") (pintype "passive"))
      (node (ref "C6") (pin "-") (pinfunction "-_-") (pintype "passive"))
      (node (ref "C7") (pin "-") (pinfunction "-_-") (pintype "passive"))
      (node (ref "C8") (pin "-") (pinfunction "-_-") (pintype "passive"))
      (node (ref "C9") (pin "-") (pinfunction "-_-") (pintype "passive"))
      (node (ref "D9") (pin "A") (pinfunction "A_A") (pintype "passive"))
      (node (ref "R11") (pin "1") (pinfunction "1_1") (pintype "passive"))
      (node (ref "T2") (pin "S1-1") (pinfunction "S1-1_S1-1") (pintype "passive"))
      (node (ref "VT2") (pin "3") (pinfunction "S_3") (pintype "passive"))
    )
    (net (code "49") (name "Net-(X2A-KL)") (class "Default")
      (node (ref "C20") (pin "+") (pinfunction "+_+") (pintype "passive"))
      (node (ref "C21") (pin "+") (pinfunction "+_+") (pintype "passive"))
      (node (ref "C22") (pin "+") (pinfunction "+_+") (pintype "passive"))
      (node (ref "C23") (pin "+") (pinfunction "+_+") (pintype "passive"))
      (node (ref "D8") (pin "A") (pinfunction "A_A") (pintype "passive"))
      (node (ref "L1") (pin "P$3") (pinfunction "2_P$3") (pintype "passive"))
      (node (ref "L1") (pin "P$4") (pinfunction "2_P$4") (pintype "passive"))
      (node (ref "R21") (pin "2") (pinfunction "2_2") (pintype "passive"))
      (node (ref "R23") (pin "2") (pinfunction "2_2") (pintype "passive"))
      (node (ref "X2") (pin "P$1") (pinfunction "KL_P$1") (pintype "passive"))
    )
    (net (code "50") (name "TR-OUT1") (class "Default")
      (node (ref "D4") (pin "C") (pinfunction "C_C") (pintype "passive"))
      (node (ref "D5") (pin "A") (pinfunction "A_A") (pintype "passive"))
      (node (ref "T3") (pin "10") (pinfunction "S1-2_10") (pintype "passive"))
      (node (ref "T3") (pin "11") (pinfunction "S1-2_11") (pintype "passive"))
      (node (ref "T3") (pin "9") (pinfunction "S1-2_9") (pintype "passive"))
    )
    (net (code "51") (name "TR-OUT2") (class "Default")
      (node (ref "D6") (pin "A") (pinfunction "A_A") (pintype "passive"))
      (node (ref "D7") (pin "C") (pinfunction "C_C") (pintype "passive"))
      (node (ref "T3") (pin "14") (pinfunction "S1-1_14") (pintype "passive"))
      (node (ref "T3") (pin "15") (pinfunction "S1-1_15") (pintype "passive"))
      (node (ref "T3") (pin "16") (pinfunction "S1-1_16") (pintype "passive"))
    )
    (net (code "52") (name "unconnected-(U1-OSC.OUT-Pad4)") (class "Default")
      (node (ref "U1") (pin "4") (pinfunction "OSC.OUT_4") (pintype "output"))
    )
    (net (code "53") (name "unconnected-(U1-SHDN-Pad10)") (class "Default")
      (node (ref "U1") (pin "10") (pinfunction "SHDN_10") (pintype "input"))
    )
    (net (code "54") (name "unconnected-(U1-SYNC-Pad3)") (class "Default")
      (node (ref "U1") (pin "3") (pinfunction "SYNC_3") (pintype "passive"))
    )
  )
)
